# LoRaPi-0.net
KiCad netlist of a schematic drawn in EAGLE
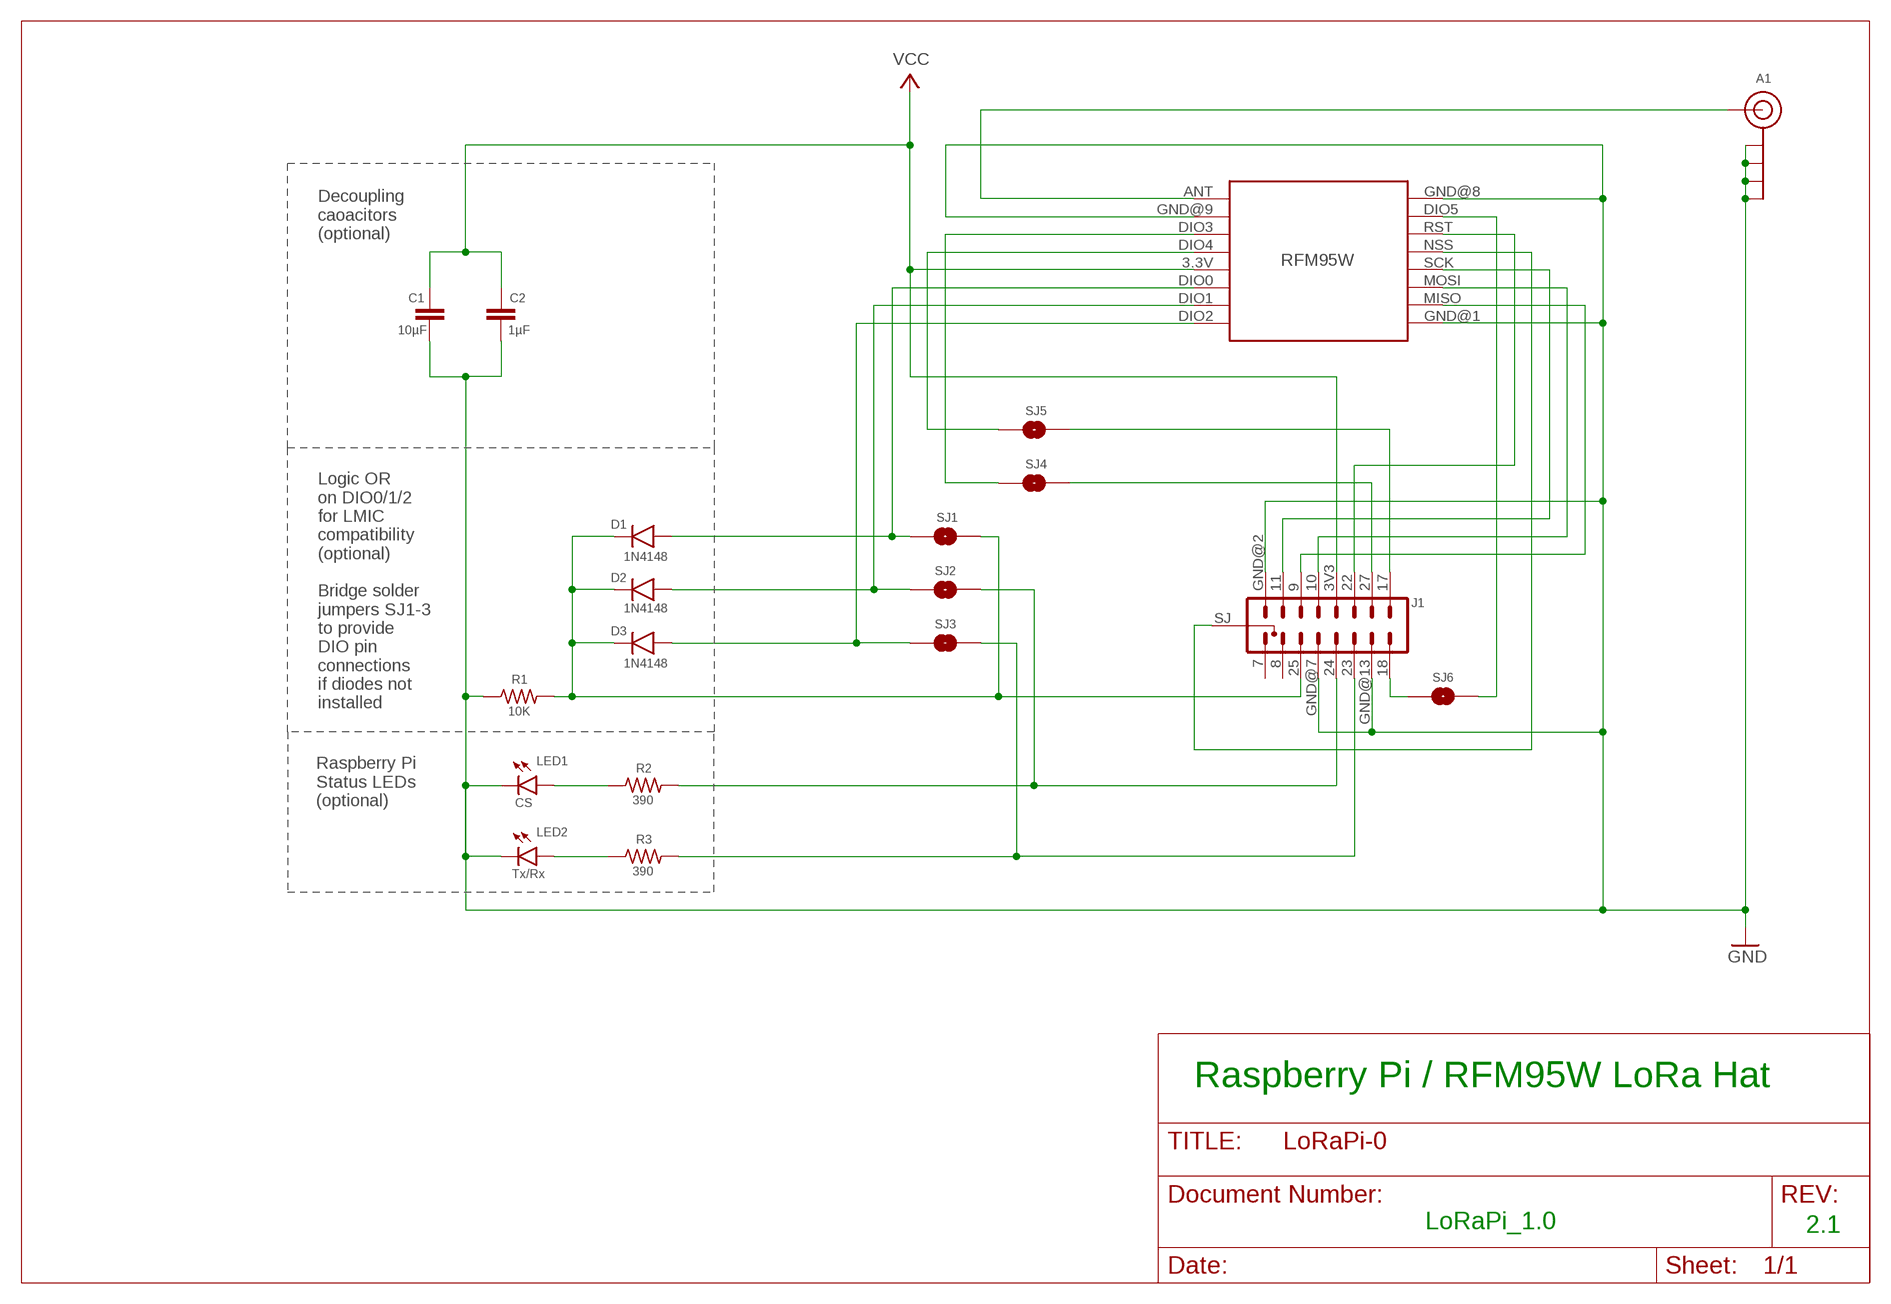
[diagram p0: schematic, sheet 1]

(export (version "E")
  (design (tool "Eeschema 10.0.6"))
  (components
    (comp (ref "A1")
      (value "U.FL-SMA-EDGE-COMBO")
      (footprint "eagle-import:U.FL-SMA-EDGE-COMBO")
      (libsource (lib "eagle-import") (part "U.FL-SMA-EDGE-COMBO"))
    )
    (comp (ref "C1")
      (value "10µF")
      (footprint "eagle-import:C0805")
      (libsource (lib "eagle-import") (part "CAPACITOR"))
    )
    (comp (ref "C2")
      (value "1µF")
      (footprint "eagle-import:C0805")
      (libsource (lib "eagle-import") (part "CAPACITOR"))
    )
    (comp (ref "D1")
      (value "1N4148")
      (footprint "eagle-import:SOD-123")
      (libsource (lib "eagle-import") (part "1N4148SMD"))
    )
    (comp (ref "D2")
      (value "1N4148")
      (footprint "eagle-import:SOD-123")
      (libsource (lib "eagle-import") (part "1N4148SMD"))
    )
    (comp (ref "D3")
      (value "1N4148")
      (footprint "eagle-import:SOD-123")
      (libsource (lib "eagle-import") (part "1N4148SMD"))
    )
    (comp (ref "J1")
      (value "HEADER-2X8-RFM95W-PI")
      (footprint "eagle-import:CONN_2X8-RFM-PI")
      (libsource (lib "eagle-import") (part "HEADER-2X8-RFM95W-PI"))
    )
    (comp (ref "LED1")
      (value "CS")
      (footprint "eagle-import:CHIP-LED0805")
      (libsource (lib "eagle-import") (part "LEDCHIP-LED0805"))
    )
    (comp (ref "LED2")
      (value "Tx/Rx")
      (footprint "eagle-import:CHIP-LED0805")
      (libsource (lib "eagle-import") (part "LEDCHIP-LED0805"))
    )
    (comp (ref "R1")
      (value "10K")
      (footprint "eagle-import:R0805")
      (libsource (lib "eagle-import") (part "R-US_R0805"))
    )
    (comp (ref "R2")
      (value "390")
      (footprint "eagle-import:R0805")
      (libsource (lib "eagle-import") (part "R-US_R0805"))
    )
    (comp (ref "R3")
      (value "390")
      (footprint "eagle-import:R0805")
      (libsource (lib "eagle-import") (part "R-US_R0805"))
    )
    (comp (ref "RFM95W")
      (value "RFM95W-LORA")
      (footprint "eagle-import:RFM95W-LORA")
      (libsource (lib "eagle-import") (part "RFM95W-LORA"))
    )
    (comp (ref "SJ1") (value "SJ") (footprint "eagle-import:SJ") (libsource (lib "eagle-import") (part "SJ")))
    (comp (ref "SJ2") (value "SJ") (footprint "eagle-import:SJ") (libsource (lib "eagle-import") (part "SJ")))
    (comp (ref "SJ3") (value "SJ") (footprint "eagle-import:SJ") (libsource (lib "eagle-import") (part "SJ")))
    (comp (ref "SJ4") (value "SJ") (footprint "eagle-import:SJ") (libsource (lib "eagle-import") (part "SJ")))
    (comp (ref "SJ5") (value "SJ") (footprint "eagle-import:SJ") (libsource (lib "eagle-import") (part "SJ")))
    (comp (ref "SJ6") (value "SJ") (footprint "eagle-import:SJ") (libsource (lib "eagle-import") (part "SJ")))
  )
  (nets
    (net (code "1") (name "GND") (class "Default")
      (node (ref "A1") (pin "GND@1A") (pinfunction "GND_GND@1A") (pintype "bidirectional"))
      (node (ref "A1") (pin "GND@1B") (pinfunction "GND_GND@1B") (pintype "bidirectional"))
      (node (ref "A1") (pin "GND@2A") (pinfunction "GND_GND@2A") (pintype "bidirectional"))
      (node (ref "A1") (pin "GND@2B") (pinfunction "GND_GND@2B") (pintype "bidirectional"))
      (node (ref "C1") (pin "2") (pinfunction "2_2") (pintype "passive"))
      (node (ref "C2") (pin "2") (pinfunction "2_2") (pintype "passive"))
      (node (ref "J1") (pin "GND@13") (pinfunction "15_GND@13") (pintype "passive"))
      (node (ref "J1") (pin "GND@2") (pinfunction "8_GND@2") (pintype "passive"))
      (node (ref "J1") (pin "GND@7") (pinfunction "12_GND@7") (pintype "passive"))
      (node (ref "LED1") (pin "C") (pinfunction "C_C") (pintype "passive"))
      (node (ref "LED2") (pin "C") (pinfunction "C_C") (pintype "passive"))
      (node (ref "R1") (pin "1") (pinfunction "1_1") (pintype "passive"))
      (node (ref "RFM95W") (pin "GND@1") (pinfunction "GND.1_GND@1") (pintype "power_in"))
      (node (ref "RFM95W") (pin "GND@8") (pinfunction "GND.2_GND@8") (pintype "power_in"))
      (node (ref "RFM95W") (pin "GND@9") (pinfunction "GND.3_GND@9") (pintype "power_in"))
    )
    (net (code "2") (name "Net-(A1-PadSIG)") (class "Default")
      (node (ref "A1") (pin "SIG") (pinfunction "SIG_SIG") (pintype "bidirectional"))
      (node (ref "RFM95W") (pin "ANT") (pinfunction "ANT_ANT") (pintype "passive"))
    )
    (net (code "3") (name "Net-(D1-Pad2)") (class "Default")
      (node (ref "D1") (pin "2") (pinfunction "2_2") (pintype "bidirectional"))
      (node (ref "RFM95W") (pin "DIO0") (pinfunction "DIO0_DIO0") (pintype "bidirectional"))
      (node (ref "SJ1") (pin "1") (pinfunction "1_1") (pintype "passive"))
    )
    (net (code "4") (name "Net-(D2-Pad2)") (class "Default")
      (node (ref "D2") (pin "2") (pinfunction "2_2") (pintype "bidirectional"))
      (node (ref "RFM95W") (pin "DIO1") (pinfunction "DIO1_DIO1") (pintype "bidirectional"))
      (node (ref "SJ2") (pin "1") (pinfunction "1_1") (pintype "passive"))
    )
    (net (code "5") (name "Net-(D3-Pad2)") (class "Default")
      (node (ref "D3") (pin "2") (pinfunction "2_2") (pintype "bidirectional"))
      (node (ref "RFM95W") (pin "DIO2") (pinfunction "DIO2_DIO2") (pintype "bidirectional"))
      (node (ref "SJ3") (pin "1") (pinfunction "1_1") (pintype "passive"))
    )
    (net (code "6") (name "Net-(J1-1)") (class "Default")
      (node (ref "J1") (pin "17") (pinfunction "1_17") (pintype "passive"))
      (node (ref "SJ5") (pin "2") (pinfunction "2_2") (pintype "passive"))
    )
    (net (code "7") (name "Net-(J1-2)") (class "Default")
      (node (ref "J1") (pin "27") (pinfunction "2_27") (pintype "passive"))
      (node (ref "SJ4") (pin "2") (pinfunction "2_2") (pintype "passive"))
    )
    (net (code "8") (name "Net-(J1-3)") (class "Default")
      (node (ref "J1") (pin "22") (pinfunction "3_22") (pintype "passive"))
      (node (ref "RFM95W") (pin "RST") (pinfunction "RST_RST") (pintype "bidirectional"))
    )
    (net (code "9") (name "Net-(J1-5)") (class "Default")
      (node (ref "J1") (pin "10") (pinfunction "5_10") (pintype "passive"))
      (node (ref "RFM95W") (pin "MOSI") (pinfunction "MOSI_MOSI") (pintype "bidirectional"))
    )
    (net (code "10") (name "Net-(J1-6)") (class "Default")
      (node (ref "J1") (pin "9") (pinfunction "6_9") (pintype "passive"))
      (node (ref "RFM95W") (pin "MISO") (pinfunction "MISO_MISO") (pintype "bidirectional"))
    )
    (net (code "11") (name "Net-(J1-7)") (class "Default")
      (node (ref "J1") (pin "11") (pinfunction "7_11") (pintype "passive"))
      (node (ref "RFM95W") (pin "SCK") (pinfunction "SCK_SCK") (pintype "bidirectional"))
    )
    (net (code "12") (name "Net-(J1-8-9)") (class "Default")
      (node (ref "J1") (pin "SJ") (pinfunction "8-9_SJ") (pintype "passive"))
      (node (ref "RFM95W") (pin "NSS") (pinfunction "NSS_NSS") (pintype "bidirectional"))
    )
    (net (code "13") (name "Net-(J1-11)") (class "Default")
      (node (ref "D1") (pin "1") (pinfunction "1_1") (pintype "bidirectional"))
      (node (ref "D2") (pin "1") (pinfunction "1_1") (pintype "bidirectional"))
      (node (ref "D3") (pin "1") (pinfunction "1_1") (pintype "bidirectional"))
      (node (ref "J1") (pin "25") (pinfunction "11_25") (pintype "passive"))
      (node (ref "R1") (pin "2") (pinfunction "2_2") (pintype "passive"))
      (node (ref "SJ1") (pin "2") (pinfunction "2_2") (pintype "passive"))
    )
    (net (code "14") (name "Net-(J1-13)") (class "Default")
      (node (ref "J1") (pin "24") (pinfunction "13_24") (pintype "passive"))
      (node (ref "R2") (pin "2") (pinfunction "2_2") (pintype "passive"))
      (node (ref "SJ2") (pin "2") (pinfunction "2_2") (pintype "passive"))
    )
    (net (code "15") (name "Net-(J1-14)") (class "Default")
      (node (ref "J1") (pin "23") (pinfunction "14_23") (pintype "passive"))
      (node (ref "R3") (pin "2") (pinfunction "2_2") (pintype "passive"))
      (node (ref "SJ3") (pin "2") (pinfunction "2_2") (pintype "passive"))
    )
    (net (code "16") (name "Net-(J1-16)") (class "Default")
      (node (ref "J1") (pin "18") (pinfunction "16_18") (pintype "passive"))
      (node (ref "SJ6") (pin "1") (pinfunction "1_1") (pintype "passive"))
    )
    (net (code "17") (name "Net-(LED1-PadA)") (class "Default")
      (node (ref "LED1") (pin "A") (pinfunction "A_A") (pintype "passive"))
      (node (ref "R2") (pin "1") (pinfunction "1_1") (pintype "passive"))
    )
    (net (code "18") (name "Net-(LED2-PadA)") (class "Default")
      (node (ref "LED2") (pin "A") (pinfunction "A_A") (pintype "passive"))
      (node (ref "R3") (pin "1") (pinfunction "1_1") (pintype "passive"))
    )
    (net (code "19") (name "Net-(RFM95W-PadDIO3)") (class "Default")
      (node (ref "RFM95W") (pin "DIO3") (pinfunction "DIO3_DIO3") (pintype "bidirectional"))
      (node (ref "SJ4") (pin "1") (pinfunction "1_1") (pintype "passive"))
    )
    (net (code "20") (name "Net-(RFM95W-PadDIO4)") (class "Default")
      (node (ref "RFM95W") (pin "DIO4") (pinfunction "DIO4_DIO4") (pintype "bidirectional"))
      (node (ref "SJ5") (pin "1") (pinfunction "1_1") (pintype "passive"))
    )
    (net (code "21") (name "Net-(RFM95W-PadDIO5)") (class "Default")
      (node (ref "RFM95W") (pin "DIO5") (pinfunction "DIO5_DIO5") (pintype "bidirectional"))
      (node (ref "SJ6") (pin "2") (pinfunction "2_2") (pintype "passive"))
    )
    (net (code "22") (name "VCC") (class "Default")
      (node (ref "C1") (pin "1") (pinfunction "1_1") (pintype "passive"))
      (node (ref "C2") (pin "1") (pinfunction "1_1") (pintype "passive"))
      (node (ref "J1") (pin "3V3") (pinfunction "4_3V3") (pintype "passive"))
      (node (ref "RFM95W") (pin "3.3V") (pinfunction "3.3V_3.3V") (pintype "power_in"))
    )
    (net (code "23") (name "unconnected-(J1-9-Pad7)") (class "Default")
      (node (ref "J1") (pin "7") (pinfunction "9_7") (pintype "passive"))
    )
    (net (code "24") (name "unconnected-(J1-10-Pad8)") (class "Default")
      (node (ref "J1") (pin "8") (pinfunction "10_8") (pintype "passive"))
    )
  )
)
